# Remote_Schematic.net
KiCad netlist of a schematic drawn in Altium Designer
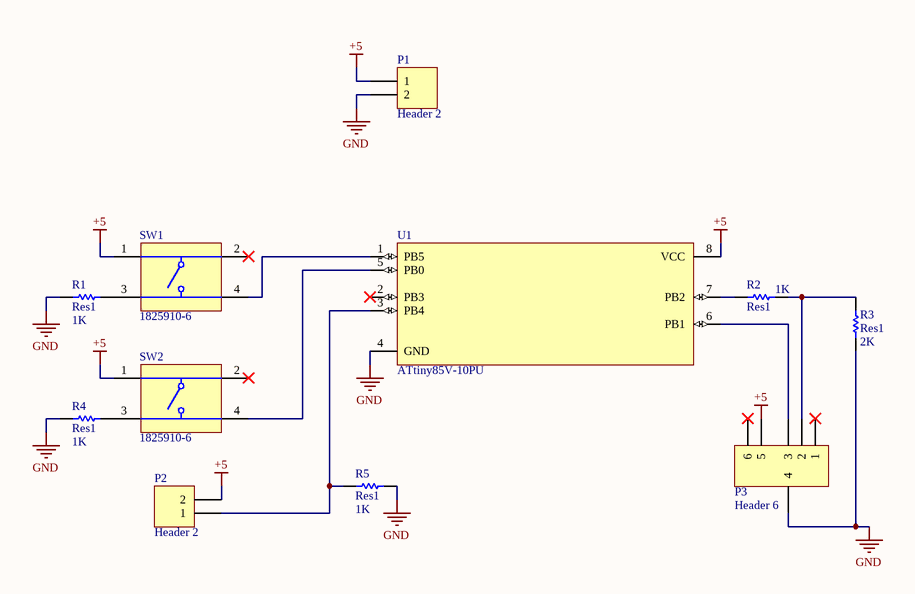
[diagram p0: Remote_Schematic.SchDoc]

(export (version "E")
  (design (tool "Eeschema 10.0.6"))
  (components
    (comp (ref "P1")
      (value "Header 2")
      (footprint "HDR1X2")
      (description "Header, 2-Pin")
      (fields (field (name "PUBLISHER") "Altium Limited"))
      (libsource (lib "") (part "Header 2_1"))
    )
    (comp (ref "P2")
      (value "Header 2")
      (footprint "HDR1X2")
      (description "Header, 2-Pin")
      (fields (field (name "PUBLISHER") "Altium Limited"))
      (libsource (lib "Miscellaneous Connectors") (part "Header 2"))
    )
    (comp (ref "P3")
      (value "Header 6")
      (footprint "HDR1X6")
      (description "Header, 6-Pin")
      (fields (field (name "PUBLISHER") "Altium Limited"))
      (libsource (lib "Miscellaneous Connectors") (part "Header 6"))
    )
    (comp (ref "R1")
      (value "Res1")
      (footprint "AXIAL-0.3")
      (description "Resistor")
      (fields (field (name "ALTIUM_VALUE") "1K") (field (name "PUBLISHER") "Altium Limited"))
      (libsource (lib "Miscellaneous Devices") (part "Res1"))
    )
    (comp (ref "R2")
      (value "Res1")
      (footprint "AXIAL-0.3")
      (description "Resistor")
      (fields (field (name "ALTIUM_VALUE") "1K") (field (name "PUBLISHER") "Altium Limited"))
      (libsource (lib "Miscellaneous Devices") (part "Res1"))
    )
    (comp (ref "R3")
      (value "Res1")
      (footprint "AXIAL-0.3")
      (description "Resistor")
      (fields (field (name "ALTIUM_VALUE") "2K") (field (name "PUBLISHER") "Altium Limited"))
      (libsource (lib "Miscellaneous Devices") (part "Res1"))
    )
    (comp (ref "R4")
      (value "Res1")
      (footprint "AXIAL-0.3")
      (description "Resistor")
      (fields (field (name "ALTIUM_VALUE") "1K") (field (name "PUBLISHER") "Altium Limited"))
      (libsource (lib "Miscellaneous Devices") (part "Res1"))
    )
    (comp (ref "R5")
      (value "Res1")
      (footprint "AXIAL-0.3")
      (description "Resistor")
      (fields (field (name "ALTIUM_VALUE") "1K") (field (name "PUBLISHER") "Altium Limited"))
      (libsource (lib "Miscellaneous Devices") (part "Res1"))
    )
    (comp (ref "SW1")
      (value "1825910-6")
      (footprint "TECO-1825910-6_V")
      (description "Tact Switch, SPST-NO, 0.05 A, -35 to 85 degC, 4-Pin THD, RoHS, Bulk")
      (fields (field (name "MANUFACTURER") "TE Connectivity"))
      (libsource (lib "Altium Content Vault") (part "SW-SPST-4_A"))
    )
    (comp (ref "SW2")
      (value "1825910-6")
      (footprint "TECO-1825910-6_V")
      (description "Tact Switch, SPST-NO, 0.05 A, -35 to 85 degC, 4-Pin THD, RoHS, Bulk")
      (fields (field (name "MANUFACTURER") "TE Connectivity"))
      (libsource (lib "Altium Content Vault") (part "SW-SPST-4_A"))
    )
    (comp (ref "U1")
      (value "ATtiny85V-10PU")
      (footprint "8P3")
      (libsource (lib "Altium Content Vault") (part "MC-8B-ATT25-IL8"))
    )
  )
  (nets
    (net (code "1") (name "+5") (class "Default")
      (node (ref "P1") (pin "1") (pinfunction "1_1") (pintype "passive"))
      (node (ref "P2") (pin "2") (pinfunction "2_2") (pintype "passive"))
      (node (ref "P3") (pin "5") (pinfunction "5_5") (pintype "passive"))
      (node (ref "SW1") (pin "1") (pinfunction "1_1") (pintype "passive"))
      (node (ref "SW2") (pin "1") (pinfunction "1_1") (pintype "passive"))
      (node (ref "U1") (pin "8") (pinfunction "VCC_8") (pintype "power_in"))
    )
    (net (code "2") (name "GND") (class "Default")
      (node (ref "P1") (pin "2") (pinfunction "2_2") (pintype "passive"))
      (node (ref "P3") (pin "4") (pinfunction "4_4") (pintype "passive"))
      (node (ref "R1") (pin "2") (pinfunction "2_2") (pintype "passive"))
      (node (ref "R3") (pin "2") (pinfunction "2_2") (pintype "passive"))
      (node (ref "R4") (pin "2") (pinfunction "2_2") (pintype "passive"))
      (node (ref "R5") (pin "1") (pinfunction "1_1") (pintype "passive"))
      (node (ref "U1") (pin "4") (pinfunction "GND_4") (pintype "power_in"))
    )
    (net (code "3") (name "Net-(P3-Pad2)") (class "Default")
      (node (ref "P3") (pin "2") (pinfunction "2_2") (pintype "passive"))
      (node (ref "R2") (pin "2") (pinfunction "2_2") (pintype "passive"))
      (node (ref "R3") (pin "1") (pinfunction "1_1") (pintype "passive"))
    )
    (net (code "4") (name "Net-(R1-Pad1)") (class "Default")
      (node (ref "R1") (pin "1") (pinfunction "1_1") (pintype "passive"))
      (node (ref "SW1") (pin "3") (pinfunction "3_3") (pintype "passive"))
    )
    (net (code "5") (name "Net-(R4-Pad1)") (class "Default")
      (node (ref "R4") (pin "1") (pinfunction "1_1") (pintype "passive"))
      (node (ref "SW2") (pin "3") (pinfunction "3_3") (pintype "passive"))
    )
    (net (code "6") (name "Net-(U1-PB0)") (class "Default")
      (node (ref "SW2") (pin "4") (pinfunction "4_4") (pintype "passive"))
      (node (ref "U1") (pin "5") (pinfunction "PB0_5") (pintype "bidirectional"))
    )
    (net (code "7") (name "Net-(U1-PB1)") (class "Default")
      (node (ref "P3") (pin "3") (pinfunction "3_3") (pintype "passive"))
      (node (ref "U1") (pin "6") (pinfunction "PB1_6") (pintype "bidirectional"))
    )
    (net (code "8") (name "Net-(U1-PB2)") (class "Default")
      (node (ref "R2") (pin "1") (pinfunction "1_1") (pintype "passive"))
      (node (ref "U1") (pin "7") (pinfunction "PB2_7") (pintype "bidirectional"))
    )
    (net (code "9") (name "Net-(U1-PB4)") (class "Default")
      (node (ref "P2") (pin "1") (pinfunction "1_1") (pintype "passive"))
      (node (ref "R5") (pin "2") (pinfunction "2_2") (pintype "passive"))
      (node (ref "U1") (pin "3") (pinfunction "PB4_3") (pintype "bidirectional"))
    )
    (net (code "10") (name "Net-(U1-PB5)") (class "Default")
      (node (ref "SW1") (pin "4") (pinfunction "4_4") (pintype "passive"))
      (node (ref "U1") (pin "1") (pinfunction "PB5_1") (pintype "bidirectional"))
    )
    (net (code "11") (name "unconnected-(P3-Pad1)") (class "Default")
      (node (ref "P3") (pin "1") (pinfunction "1_1") (pintype "passive+no_connect"))
    )
    (net (code "12") (name "unconnected-(P3-Pad6)") (class "Default")
      (node (ref "P3") (pin "6") (pinfunction "6_6") (pintype "passive+no_connect"))
    )
    (net (code "13") (name "unconnected-(SW1-Pad2)") (class "Default")
      (node (ref "SW1") (pin "2") (pinfunction "2_2") (pintype "passive+no_connect"))
    )
    (net (code "14") (name "unconnected-(SW2-Pad2)") (class "Default")
      (node (ref "SW2") (pin "2") (pinfunction "2_2") (pintype "passive+no_connect"))
    )
    (net (code "15") (name "unconnected-(U1-PB3-Pad2)") (class "Default")
      (node (ref "U1") (pin "2") (pinfunction "PB3_2") (pintype "bidirectional+no_connect"))
    )
  )
)
